# MCORD_Hub.net
KiCad netlist of a schematic drawn in Altium Designer
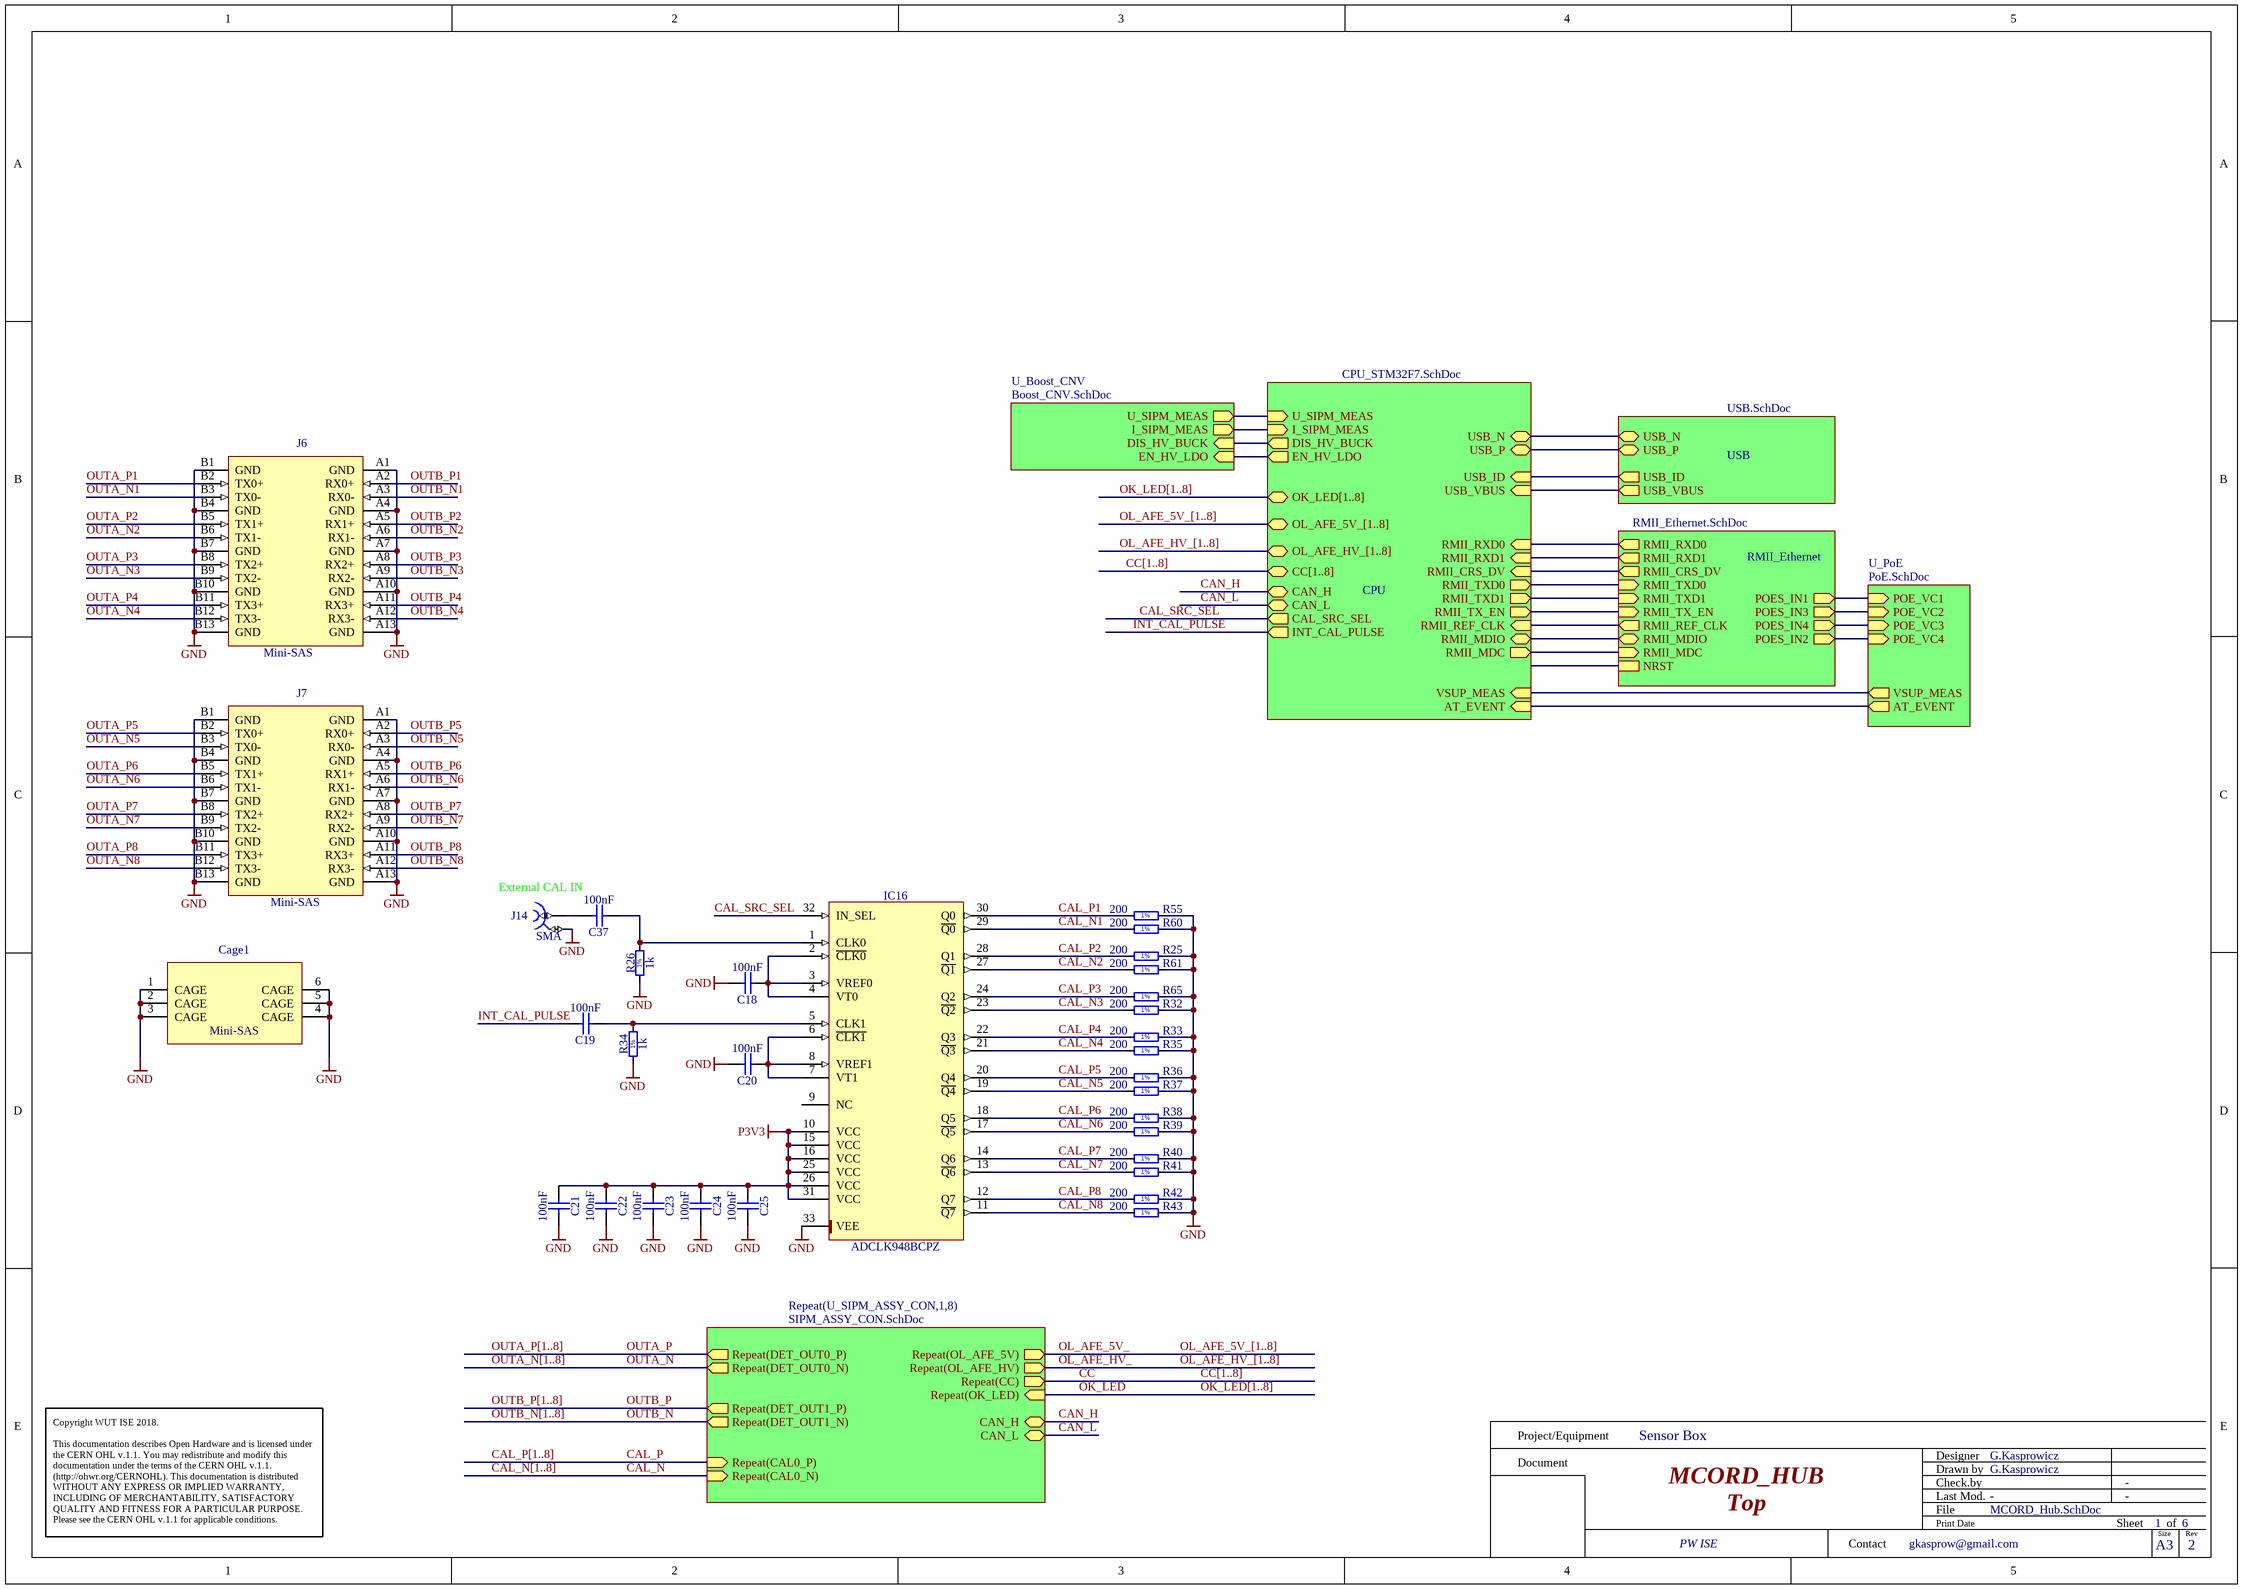
[diagram p0: MCORD_Hub.SchDoc]

(export (version "E")
  (design (tool "Eeschema 10.0.6"))
  (components
    (comp (ref "C18")
      (value "100nF")
      (footprint "CAPC1005X55N")
      (description "Non-polarised capacitor")
      (fields
        (field (name "PART NUMBER") "CC0402_100NF_16V_10%_X7R")
        (field (name "VOLTAGE") "16V")
        (field (name "AUTHOR") "CERN DEM JLC")
      )
      (libsource (lib "Capacitors") (part "Capacitor - non polarized"))
    )
    (comp (ref "C19")
      (value "100nF")
      (footprint "CAPC1005X55N")
      (description "Non-polarised capacitor")
      (fields
        (field (name "PART NUMBER") "CC0402_100NF_16V_10%_X7R")
        (field (name "VOLTAGE") "16V")
        (field (name "AUTHOR") "CERN DEM JLC")
      )
      (libsource (lib "Capacitors") (part "Capacitor - non polarized"))
    )
    (comp (ref "C20")
      (value "100nF")
      (footprint "CAPC1005X55N")
      (description "Non-polarised capacitor")
      (fields
        (field (name "PART NUMBER") "CC0402_100NF_16V_10%_X7R")
        (field (name "VOLTAGE") "16V")
        (field (name "AUTHOR") "CERN DEM JLC")
      )
      (libsource (lib "Capacitors") (part "Capacitor - non polarized"))
    )
    (comp (ref "C21")
      (value "100nF")
      (footprint "CAPC1005X55N")
      (description "Non-polarised capacitor")
      (fields
        (field (name "PART NUMBER") "CC0402_100NF_16V_10%_X7R")
        (field (name "VOLTAGE") "16V")
        (field (name "AUTHOR") "CERN DEM JLC")
      )
      (libsource (lib "Capacitors") (part "Capacitor - non polarized"))
    )
    (comp (ref "C22")
      (value "100nF")
      (footprint "CAPC1005X55N")
      (description "Non-polarised capacitor")
      (fields
        (field (name "PART NUMBER") "CC0402_100NF_16V_10%_X7R")
        (field (name "VOLTAGE") "16V")
        (field (name "AUTHOR") "CERN DEM JLC")
      )
      (libsource (lib "Capacitors") (part "Capacitor - non polarized"))
    )
    (comp (ref "C23")
      (value "100nF")
      (footprint "CAPC1005X55N")
      (description "Non-polarised capacitor")
      (fields
        (field (name "PART NUMBER") "CC0402_100NF_16V_10%_X7R")
        (field (name "VOLTAGE") "16V")
        (field (name "AUTHOR") "CERN DEM JLC")
      )
      (libsource (lib "Capacitors") (part "Capacitor - non polarized"))
    )
    (comp (ref "C24")
      (value "100nF")
      (footprint "CAPC1005X55N")
      (description "Non-polarised capacitor")
      (fields
        (field (name "PART NUMBER") "CC0402_100NF_16V_10%_X7R")
        (field (name "VOLTAGE") "16V")
        (field (name "AUTHOR") "CERN DEM JLC")
      )
      (libsource (lib "Capacitors") (part "Capacitor - non polarized"))
    )
    (comp (ref "C25")
      (value "100nF")
      (footprint "CAPC1005X55N")
      (description "Non-polarised capacitor")
      (fields
        (field (name "PART NUMBER") "CC0402_100NF_16V_10%_X7R")
        (field (name "VOLTAGE") "16V")
        (field (name "AUTHOR") "CERN DEM JLC")
      )
      (libsource (lib "Capacitors") (part "Capacitor - non polarized"))
    )
    (comp (ref "C37")
      (value "100nF")
      (footprint "CAPC1005X55N")
      (description "Non-polarised capacitor")
      (fields
        (field (name "PART NUMBER") "CC0402_100NF_16V_10%_X7R")
        (field (name "VOLTAGE") "16V")
        (field (name "AUTHOR") "CERN DEM JLC")
      )
      (libsource (lib "Capacitors") (part "Capacitor - non polarized"))
    )
    (comp (ref "Cage1")
      (value "Mini-SAS")
      (footprint "TYCO_1888321-2")
      (description "Mini-SAS Cage (6Pins)")
      (fields
        (field (name "PART NUMBER") "TYCO_1888321-2")
        (field (name "MANUFACTURER") "TYCO ELECTRONICS")
        (field (name "AUTHOR") "CERN DEM BC")
      )
      (libsource (lib "Connectors") (part "Mini-SAS Cage (6Pins)"))
    )
    (comp (ref "IC16")
      (value "ADCLK948BCPZ")
      (footprint "QFN50P500X500X80-33N-S285")
      (description "Two Selectable Inputs, 8 LVPECL Outputs, SiGe Clock Fanout Buffer")
      (fields (field (name "MANUFACTURER") "ANALOG DEVICES") (field (name "AUTHOR") "CERN DEM MR"))
      (libsource (lib "ICs And Semiconductors") (part "ADCLK948"))
    )
    (comp (ref "J6")
      (value "Mini-SAS")
      (footprint "TYCO_1761987-7")
      (description "26 Position Mini-Sas Connector (Quad Small Form-Factor SFF-8088)")
      (fields
        (field (name "PART NUMBER") "TYCO_1761987-7")
        (field (name "MANUFACTURER") "TYCO ELECTRONICS")
        (field (name "AUTHOR") "CERN DEM MR")
      )
      (libsource (lib "Connectors") (part "Mini-SAS"))
    )
    (comp (ref "J7")
      (value "Mini-SAS")
      (footprint "TYCO_1761987-7")
      (description "26 Position Mini-Sas Connector (Quad Small Form-Factor SFF-8088)")
      (fields
        (field (name "PART NUMBER") "TYCO_1761987-7")
        (field (name "MANUFACTURER") "TYCO ELECTRONICS")
        (field (name "AUTHOR") "CERN DEM MR")
      )
      (libsource (lib "Connectors") (part "Mini-SAS"))
    )
    (comp (ref "J14")
      (value "SMA")
      (footprint "RF249BT0050GHDW")
      (description "50 Ohm Through Hole SMA Right Angle PCB Jack")
      (fields
        (field (name "PART NUMBER") "AdamTech_RF249BT0050GHDW")
        (field (name "MANUFACTURER") "AdamTech / Molex")
        (field (name "AUTHOR") "GK")
      )
      (libsource (lib "LIBRARY_SCH") (part "CON_SMA_RF249BT0050GHDW"))
    )
    (comp (ref "R25")
      (value "200")
      (footprint "RESC1005X40N")
      (description "Resistor - 1%")
      (fields
        (field (name "PART NUMBER") "R0402_200R_1%_0.0625W_100PPM")
        (field (name "POWER") "0.0625W")
        (field (name "AUTHOR") "CERN DEM JLC")
      )
      (libsource (lib "Resistors") (part "Resistor - 1%"))
    )
    (comp (ref "R26")
      (value "1k")
      (footprint "RESC1005X40N")
      (description "Resistor - 1%")
      (fields
        (field (name "PART NUMBER") "R0402_1K_1%_0.0625W_100PPM")
        (field (name "POWER") "0.0625W")
        (field (name "AUTHOR") "CERN DEM JLC")
      )
      (libsource (lib "Resistors") (part "Resistor - 1%"))
    )
    (comp (ref "R32")
      (value "200")
      (footprint "RESC1005X40N")
      (description "Resistor - 1%")
      (fields
        (field (name "PART NUMBER") "R0402_200R_1%_0.0625W_100PPM")
        (field (name "POWER") "0.0625W")
        (field (name "AUTHOR") "CERN DEM JLC")
      )
      (libsource (lib "Resistors") (part "Resistor - 1%"))
    )
    (comp (ref "R33")
      (value "200")
      (footprint "RESC1005X40N")
      (description "Resistor - 1%")
      (fields
        (field (name "PART NUMBER") "R0402_200R_1%_0.0625W_100PPM")
        (field (name "POWER") "0.0625W")
        (field (name "AUTHOR") "CERN DEM JLC")
      )
      (libsource (lib "Resistors") (part "Resistor - 1%"))
    )
    (comp (ref "R34")
      (value "1k")
      (footprint "RESC1005X40N")
      (description "Resistor - 1%")
      (fields
        (field (name "PART NUMBER") "R0402_1K_1%_0.0625W_100PPM")
        (field (name "POWER") "0.0625W")
        (field (name "AUTHOR") "CERN DEM JLC")
      )
      (libsource (lib "Resistors") (part "Resistor - 1%"))
    )
    (comp (ref "R35")
      (value "200")
      (footprint "RESC1005X40N")
      (description "Resistor - 1%")
      (fields
        (field (name "PART NUMBER") "R0402_200R_1%_0.0625W_100PPM")
        (field (name "POWER") "0.0625W")
        (field (name "AUTHOR") "CERN DEM JLC")
      )
      (libsource (lib "Resistors") (part "Resistor - 1%"))
    )
    (comp (ref "R36")
      (value "200")
      (footprint "RESC1005X40N")
      (description "Resistor - 1%")
      (fields
        (field (name "PART NUMBER") "R0402_200R_1%_0.0625W_100PPM")
        (field (name "POWER") "0.0625W")
        (field (name "AUTHOR") "CERN DEM JLC")
      )
      (libsource (lib "Resistors") (part "Resistor - 1%"))
    )
    (comp (ref "R37")
      (value "200")
      (footprint "RESC1005X40N")
      (description "Resistor - 1%")
      (fields
        (field (name "PART NUMBER") "R0402_200R_1%_0.0625W_100PPM")
        (field (name "POWER") "0.0625W")
        (field (name "AUTHOR") "CERN DEM JLC")
      )
      (libsource (lib "Resistors") (part "Resistor - 1%"))
    )
    (comp (ref "R38")
      (value "200")
      (footprint "RESC1005X40N")
      (description "Resistor - 1%")
      (fields
        (field (name "PART NUMBER") "R0402_200R_1%_0.0625W_100PPM")
        (field (name "POWER") "0.0625W")
        (field (name "AUTHOR") "CERN DEM JLC")
      )
      (libsource (lib "Resistors") (part "Resistor - 1%"))
    )
    (comp (ref "R39")
      (value "200")
      (footprint "RESC1005X40N")
      (description "Resistor - 1%")
      (fields
        (field (name "PART NUMBER") "R0402_200R_1%_0.0625W_100PPM")
        (field (name "POWER") "0.0625W")
        (field (name "AUTHOR") "CERN DEM JLC")
      )
      (libsource (lib "Resistors") (part "Resistor - 1%"))
    )
    (comp (ref "R40")
      (value "200")
      (footprint "RESC1005X40N")
      (description "Resistor - 1%")
      (fields
        (field (name "PART NUMBER") "R0402_200R_1%_0.0625W_100PPM")
        (field (name "POWER") "0.0625W")
        (field (name "AUTHOR") "CERN DEM JLC")
      )
      (libsource (lib "Resistors") (part "Resistor - 1%"))
    )
    (comp (ref "R41")
      (value "200")
      (footprint "RESC1005X40N")
      (description "Resistor - 1%")
      (fields
        (field (name "PART NUMBER") "R0402_200R_1%_0.0625W_100PPM")
        (field (name "POWER") "0.0625W")
        (field (name "AUTHOR") "CERN DEM JLC")
      )
      (libsource (lib "Resistors") (part "Resistor - 1%"))
    )
    (comp (ref "R42")
      (value "200")
      (footprint "RESC1005X40N")
      (description "Resistor - 1%")
      (fields
        (field (name "PART NUMBER") "R0402_200R_1%_0.0625W_100PPM")
        (field (name "POWER") "0.0625W")
        (field (name "AUTHOR") "CERN DEM JLC")
      )
      (libsource (lib "Resistors") (part "Resistor - 1%"))
    )
    (comp (ref "R43")
      (value "200")
      (footprint "RESC1005X40N")
      (description "Resistor - 1%")
      (fields
        (field (name "PART NUMBER") "R0402_200R_1%_0.0625W_100PPM")
        (field (name "POWER") "0.0625W")
        (field (name "AUTHOR") "CERN DEM JLC")
      )
      (libsource (lib "Resistors") (part "Resistor - 1%"))
    )
    (comp (ref "R55")
      (value "200")
      (footprint "RESC1005X40N")
      (description "Resistor - 1%")
      (fields
        (field (name "PART NUMBER") "R0402_200R_1%_0.0625W_100PPM")
        (field (name "POWER") "0.0625W")
        (field (name "AUTHOR") "CERN DEM JLC")
      )
      (libsource (lib "Resistors") (part "Resistor - 1%"))
    )
    (comp (ref "R60")
      (value "200")
      (footprint "RESC1005X40N")
      (description "Resistor - 1%")
      (fields
        (field (name "PART NUMBER") "R0402_200R_1%_0.0625W_100PPM")
        (field (name "POWER") "0.0625W")
        (field (name "AUTHOR") "CERN DEM JLC")
      )
      (libsource (lib "Resistors") (part "Resistor - 1%"))
    )
    (comp (ref "R61")
      (value "200")
      (footprint "RESC1005X40N")
      (description "Resistor - 1%")
      (fields
        (field (name "PART NUMBER") "R0402_200R_1%_0.0625W_100PPM")
        (field (name "POWER") "0.0625W")
        (field (name "AUTHOR") "CERN DEM JLC")
      )
      (libsource (lib "Resistors") (part "Resistor - 1%"))
    )
    (comp (ref "R65")
      (value "200")
      (footprint "RESC1005X40N")
      (description "Resistor - 1%")
      (fields
        (field (name "PART NUMBER") "R0402_200R_1%_0.0625W_100PPM")
        (field (name "POWER") "0.0625W")
        (field (name "AUTHOR") "CERN DEM JLC")
      )
      (libsource (lib "Resistors") (part "Resistor - 1%"))
    )
  )
  (nets
    (net (code "35") (name "/CAL_N1") (class "Default")
      (node (ref "IC16") (pin "29") (pinfunction "~{Q0}_29") (pintype "output"))
      (node (ref "R60") (pin "1") (pinfunction "1_1") (pintype "passive"))
    )
    (net (code "36") (name "/CAL_N2") (class "Default")
      (node (ref "IC16") (pin "27") (pinfunction "~{Q1}_27") (pintype "output"))
      (node (ref "R61") (pin "1") (pinfunction "1_1") (pintype "passive"))
    )
    (net (code "37") (name "/CAL_N3") (class "Default")
      (node (ref "IC16") (pin "23") (pinfunction "~{Q2}_23") (pintype "output"))
      (node (ref "R32") (pin "1") (pinfunction "1_1") (pintype "passive"))
    )
    (net (code "38") (name "/CAL_N4") (class "Default")
      (node (ref "IC16") (pin "21") (pinfunction "~{Q3}_21") (pintype "output"))
      (node (ref "R35") (pin "1") (pinfunction "1_1") (pintype "passive"))
    )
    (net (code "39") (name "/CAL_N5") (class "Default")
      (node (ref "IC16") (pin "19") (pinfunction "~{Q4}_19") (pintype "output"))
      (node (ref "R37") (pin "1") (pinfunction "1_1") (pintype "passive"))
    )
    (net (code "40") (name "/CAL_N6") (class "Default")
      (node (ref "IC16") (pin "17") (pinfunction "~{Q5}_17") (pintype "output"))
      (node (ref "R39") (pin "1") (pinfunction "1_1") (pintype "passive"))
    )
    (net (code "41") (name "/CAL_N7") (class "Default")
      (node (ref "IC16") (pin "13") (pinfunction "~{Q6}_13") (pintype "output"))
      (node (ref "R41") (pin "1") (pinfunction "1_1") (pintype "passive"))
    )
    (net (code "42") (name "/CAL_N8") (class "Default")
      (node (ref "IC16") (pin "11") (pinfunction "~{Q7}_11") (pintype "output"))
      (node (ref "R43") (pin "1") (pinfunction "1_1") (pintype "passive"))
    )
    (net (code "45") (name "/CAL_P1") (class "Default")
      (node (ref "IC16") (pin "30") (pinfunction "Q0_30") (pintype "output"))
      (node (ref "R55") (pin "1") (pinfunction "1_1") (pintype "passive"))
    )
    (net (code "46") (name "/CAL_P2") (class "Default")
      (node (ref "IC16") (pin "28") (pinfunction "Q1_28") (pintype "output"))
      (node (ref "R25") (pin "1") (pinfunction "1_1") (pintype "passive"))
    )
    (net (code "47") (name "/CAL_P3") (class "Default")
      (node (ref "IC16") (pin "24") (pinfunction "Q2_24") (pintype "output"))
      (node (ref "R65") (pin "1") (pinfunction "1_1") (pintype "passive"))
    )
    (net (code "48") (name "/CAL_P4") (class "Default")
      (node (ref "IC16") (pin "22") (pinfunction "Q3_22") (pintype "output"))
      (node (ref "R33") (pin "1") (pinfunction "1_1") (pintype "passive"))
    )
    (net (code "49") (name "/CAL_P5") (class "Default")
      (node (ref "IC16") (pin "20") (pinfunction "Q4_20") (pintype "output"))
      (node (ref "R36") (pin "1") (pinfunction "1_1") (pintype "passive"))
    )
    (net (code "50") (name "/CAL_P6") (class "Default")
      (node (ref "IC16") (pin "18") (pinfunction "Q5_18") (pintype "output"))
      (node (ref "R38") (pin "1") (pinfunction "1_1") (pintype "passive"))
    )
    (net (code "51") (name "/CAL_P7") (class "Default")
      (node (ref "IC16") (pin "14") (pinfunction "Q6_14") (pintype "output"))
      (node (ref "R40") (pin "1") (pinfunction "1_1") (pintype "passive"))
    )
    (net (code "52") (name "/CAL_P8") (class "Default")
      (node (ref "IC16") (pin "12") (pinfunction "Q7_12") (pintype "output"))
      (node (ref "R42") (pin "1") (pinfunction "1_1") (pintype "passive"))
    )
    (net (code "54") (name "/CAL_SRC_SEL") (class "Default")
      (node (ref "IC16") (pin "32") (pinfunction "IN_SEL_32") (pintype "input"))
    )
    (net (code "61") (name "/INT_CAL_PULSE") (class "Default")
      (node (ref "C19") (pin "2") (pinfunction "2_2") (pintype "passive"))
    )
    (net (code "71") (name "/OUTA_N1") (class "Default")
      (node (ref "J6") (pin "B3") (pinfunction "TX0-_B3") (pintype "input"))
    )
    (net (code "72") (name "/OUTA_N2") (class "Default")
      (node (ref "J6") (pin "B6") (pinfunction "TX1-_B6") (pintype "input"))
    )
    (net (code "73") (name "/OUTA_N3") (class "Default")
      (node (ref "J6") (pin "B9") (pinfunction "TX2-_B9") (pintype "input"))
    )
    (net (code "74") (name "/OUTA_N4") (class "Default")
      (node (ref "J6") (pin "B12") (pinfunction "TX3-_B12") (pintype "input"))
    )
    (net (code "75") (name "/OUTA_N5") (class "Default")
      (node (ref "J7") (pin "B3") (pinfunction "TX0-_B3") (pintype "input"))
    )
    (net (code "76") (name "/OUTA_N6") (class "Default")
      (node (ref "J7") (pin "B6") (pinfunction "TX1-_B6") (pintype "input"))
    )
    (net (code "77") (name "/OUTA_N7") (class "Default")
      (node (ref "J7") (pin "B9") (pinfunction "TX2-_B9") (pintype "input"))
    )
    (net (code "78") (name "/OUTA_N8") (class "Default")
      (node (ref "J7") (pin "B12") (pinfunction "TX3-_B12") (pintype "input"))
    )
    (net (code "81") (name "/OUTA_P1") (class "Default")
      (node (ref "J6") (pin "B2") (pinfunction "TX0+_B2") (pintype "input"))
    )
    (net (code "82") (name "/OUTA_P2") (class "Default")
      (node (ref "J6") (pin "B5") (pinfunction "TX1+_B5") (pintype "input"))
    )
    (net (code "83") (name "/OUTA_P3") (class "Default")
      (node (ref "J6") (pin "B8") (pinfunction "TX2+_B8") (pintype "input"))
    )
    (net (code "84") (name "/OUTA_P4") (class "Default")
      (node (ref "J6") (pin "B11") (pinfunction "TX3+_B11") (pintype "input"))
    )
    (net (code "85") (name "/OUTA_P5") (class "Default")
      (node (ref "J7") (pin "B2") (pinfunction "TX0+_B2") (pintype "input"))
    )
    (net (code "86") (name "/OUTA_P6") (class "Default")
      (node (ref "J7") (pin "B5") (pinfunction "TX1+_B5") (pintype "input"))
    )
    (net (code "87") (name "/OUTA_P7") (class "Default")
      (node (ref "J7") (pin "B8") (pinfunction "TX2+_B8") (pintype "input"))
    )
    (net (code "88") (name "/OUTA_P8") (class "Default")
      (node (ref "J7") (pin "B11") (pinfunction "TX3+_B11") (pintype "input"))
    )
    (net (code "91") (name "/OUTB_N1") (class "Default")
      (node (ref "J6") (pin "A3") (pinfunction "RX0-_A3") (pintype "input"))
    )
    (net (code "92") (name "/OUTB_N2") (class "Default")
      (node (ref "J6") (pin "A6") (pinfunction "RX1-_A6") (pintype "input"))
    )
    (net (code "93") (name "/OUTB_N3") (class "Default")
      (node (ref "J6") (pin "A9") (pinfunction "RX2-_A9") (pintype "input"))
    )
    (net (code "94") (name "/OUTB_N4") (class "Default")
      (node (ref "J6") (pin "A12") (pinfunction "RX3-_A12") (pintype "input"))
    )
    (net (code "95") (name "/OUTB_N5") (class "Default")
      (node (ref "J7") (pin "A3") (pinfunction "RX0-_A3") (pintype "input"))
    )
    (net (code "96") (name "/OUTB_N6") (class "Default")
      (node (ref "J7") (pin "A6") (pinfunction "RX1-_A6") (pintype "input"))
    )
    (net (code "97") (name "/OUTB_N7") (class "Default")
      (node (ref "J7") (pin "A9") (pinfunction "RX2-_A9") (pintype "input"))
    )
    (net (code "98") (name "/OUTB_N8") (class "Default")
      (node (ref "J7") (pin "A12") (pinfunction "RX3-_A12") (pintype "input"))
    )
    (net (code "101") (name "/OUTB_P1") (class "Default")
      (node (ref "J6") (pin "A2") (pinfunction "RX0+_A2") (pintype "input"))
    )
    (net (code "102") (name "/OUTB_P2") (class "Default")
      (node (ref "J6") (pin "A5") (pinfunction "RX1+_A5") (pintype "input"))
    )
    (net (code "103") (name "/OUTB_P3") (class "Default")
      (node (ref "J6") (pin "A8") (pinfunction "RX2+_A8") (pintype "input"))
    )
    (net (code "104") (name "/OUTB_P4") (class "Default")
      (node (ref "J6") (pin "A11") (pinfunction "RX3+_A11") (pintype "input"))
    )
    (net (code "105") (name "/OUTB_P5") (class "Default")
      (node (ref "J7") (pin "A2") (pinfunction "RX0+_A2") (pintype "input"))
    )
    (net (code "106") (name "/OUTB_P6") (class "Default")
      (node (ref "J7") (pin "A5") (pinfunction "RX1+_A5") (pintype "input"))
    )
    (net (code "107") (name "/OUTB_P7") (class "Default")
      (node (ref "J7") (pin "A8") (pinfunction "RX2+_A8") (pintype "input"))
    )
    (net (code "108") (name "/OUTB_P8") (class "Default")
      (node (ref "J7") (pin "A11") (pinfunction "RX3+_A11") (pintype "input"))
    )
    (net (code "129") (name "GND") (class "Default")
      (node (ref "C18") (pin "2") (pinfunction "2_2") (pintype "passive"))
      (node (ref "C20") (pin "2") (pinfunction "2_2") (pintype "passive"))
      (node (ref "C21") (pin "2") (pinfunction "2_2") (pintype "passive"))
      (node (ref "C22") (pin "2") (pinfunction "2_2") (pintype "passive"))
      (node (ref "C23") (pin "2") (pinfunction "2_2") (pintype "passive"))
      (node (ref "C24") (pin "2") (pinfunction "2_2") (pintype "passive"))
      (node (ref "C25") (pin "2") (pinfunction "2_2") (pintype "passive"))
      (node (ref "Cage1") (pin "1") (pinfunction "CAGE_1") (pintype "power_in"))
      (node (ref "Cage1") (pin "2") (pinfunction "CAGE_2") (pintype "power_in"))
      (node (ref "Cage1") (pin "3") (pinfunction "CAGE_3") (pintype "power_in"))
      (node (ref "Cage1") (pin "4") (pinfunction "CAGE_4") (pintype "power_in"))
      (node (ref "Cage1") (pin "5") (pinfunction "CAGE_5") (pintype "power_in"))
      (node (ref "Cage1") (pin "6") (pinfunction "CAGE_6") (pintype "power_in"))
      (node (ref "IC16") (pin "33") (pinfunction "VEE_33") (pintype "power_in"))
      (node (ref "J14") (pin "2") (pinfunction "2_2") (pintype "bidirectional"))
      (node (ref "J6") (pin "A1") (pinfunction "GND_A1") (pintype "power_in"))
      (node (ref "J6") (pin "A10") (pinfunction "GND_A10") (pintype "power_in"))
      (node (ref "J6") (pin "A13") (pinfunction "GND_A13") (pintype "power_in"))
      (node (ref "J6") (pin "A4") (pinfunction "GND_A4") (pintype "power_in"))
      (node (ref "J6") (pin "A7") (pinfunction "GND_A7") (pintype "power_in"))
      (node (ref "J6") (pin "B1") (pinfunction "GND_B1") (pintype "power_in"))
      (node (ref "J6") (pin "B10") (pinfunction "GND_B10") (pintype "power_in"))
      (node (ref "J6") (pin "B13") (pinfunction "GND_B13") (pintype "power_in"))
      (node (ref "J6") (pin "B4") (pinfunction "GND_B4") (pintype "power_in"))
      (node (ref "J6") (pin "B7") (pinfunction "GND_B7") (pintype "power_in"))
      (node (ref "J7") (pin "A1") (pinfunction "GND_A1") (pintype "power_in"))
      (node (ref "J7") (pin "A10") (pinfunction "GND_A10") (pintype "power_in"))
      (node (ref "J7") (pin "A13") (pinfunction "GND_A13") (pintype "power_in"))
      (node (ref "J7") (pin "A4") (pinfunction "GND_A4") (pintype "power_in"))
      (node (ref "J7") (pin "A7") (pinfunction "GND_A7") (pintype "power_in"))
      (node (ref "J7") (pin "B1") (pinfunction "GND_B1") (pintype "power_in"))
      (node (ref "J7") (pin "B10") (pinfunction "GND_B10") (pintype "power_in"))
      (node (ref "J7") (pin "B13") (pinfunction "GND_B13") (pintype "power_in"))
      (node (ref "J7") (pin "B4") (pinfunction "GND_B4") (pintype "power_in"))
      (node (ref "J7") (pin "B7") (pinfunction "GND_B7") (pintype "power_in"))
      (node (ref "R25") (pin "2") (pinfunction "2_2") (pintype "passive"))
      (node (ref "R26") (pin "1") (pinfunction "1_1") (pintype "passive"))
      (node (ref "R32") (pin "2") (pinfunction "2_2") (pintype "passive"))
      (node (ref "R33") (pin "2") (pinfunction "2_2") (pintype "passive"))
      (node (ref "R34") (pin "1") (pinfunction "1_1") (pintype "passive"))
      (node (ref "R35") (pin "2") (pinfunction "2_2") (pintype "passive"))
      (node (ref "R36") (pin "2") (pinfunction "2_2") (pintype "passive"))
      (node (ref "R37") (pin "2") (pinfunction "2_2") (pintype "passive"))
      (node (ref "R38") (pin "2") (pinfunction "2_2") (pintype "passive"))
      (node (ref "R39") (pin "2") (pinfunction "2_2") (pintype "passive"))
      (node (ref "R40") (pin "2") (pinfunction "2_2") (pintype "passive"))
      (node (ref "R41") (pin "2") (pinfunction "2_2") (pintype "passive"))
      (node (ref "R42") (pin "2") (pinfunction "2_2") (pintype "passive"))
      (node (ref "R43") (pin "2") (pinfunction "2_2") (pintype "passive"))
      (node (ref "R55") (pin "2") (pinfunction "2_2") (pintype "passive"))
      (node (ref "R60") (pin "2") (pinfunction "2_2") (pintype "passive"))
      (node (ref "R61") (pin "2") (pinfunction "2_2") (pintype "passive"))
      (node (ref "R65") (pin "2") (pinfunction "2_2") (pintype "passive"))
    )
    (net (code "130") (name "Net-(C37-Pad2)") (class "Default")
      (node (ref "C37") (pin "2") (pinfunction "2_2") (pintype "passive"))
      (node (ref "J14") (pin "1") (pinfunction "1_1") (pintype "bidirectional"))
    )
    (net (code "131") (name "Net-(IC16-CLK0)") (class "Default")
      (node (ref "C37") (pin "1") (pinfunction "1_1") (pintype "passive"))
      (node (ref "IC16") (pin "1") (pinfunction "CLK0_1") (pintype "input"))
      (node (ref "R26") (pin "2") (pinfunction "2_2") (pintype "passive"))
    )
    (net (code "132") (name "Net-(IC16-CLK1)") (class "Default")
      (node (ref "C19") (pin "1") (pinfunction "1_1") (pintype "passive"))
      (node (ref "IC16") (pin "5") (pinfunction "CLK1_5") (pintype "input"))
      (node (ref "R34") (pin "2") (pinfunction "2_2") (pintype "passive"))
    )
    (net (code "133") (name "Net-(IC16-VREF0)") (class "Default")
      (node (ref "C18") (pin "1") (pinfunction "1_1") (pintype "passive"))
      (node (ref "IC16") (pin "2") (pinfunction "~{CLK0}_2") (pintype "input"))
      (node (ref "IC16") (pin "3") (pinfunction "VREF0_3") (pintype "input"))
      (node (ref "IC16") (pin "4") (pinfunction "VT0_4") (pintype "passive"))
    )
    (net (code "134") (name "Net-(IC16-VREF1)") (class "Default")
      (node (ref "C20") (pin "1") (pinfunction "1_1") (pintype "passive"))
      (node (ref "IC16") (pin "6") (pinfunction "~{CLK1}_6") (pintype "input"))
      (node (ref "IC16") (pin "7") (pinfunction "VT1_7") (pintype "passive"))
      (node (ref "IC16") (pin "8") (pinfunction "VREF1_8") (pintype "input"))
    )
    (net (code "135") (name "P3V3") (class "Default")
      (node (ref "C21") (pin "1") (pinfunction "1_1") (pintype "passive"))
      (node (ref "C22") (pin "1") (pinfunction "1_1") (pintype "passive"))
      (node (ref "C23") (pin "1") (pinfunction "1_1") (pintype "passive"))
      (node (ref "C24") (pin "1") (pinfunction "1_1") (pintype "passive"))
      (node (ref "C25") (pin "1") (pinfunction "1_1") (pintype "passive"))
      (node (ref "IC16") (pin "10") (pinfunction "VCC_10") (pintype "power_in"))
      (node (ref "IC16") (pin "15") (pinfunction "VCC_15") (pintype "power_in"))
      (node (ref "IC16") (pin "16") (pinfunction "VCC_16") (pintype "power_in"))
      (node (ref "IC16") (pin "25") (pinfunction "VCC_25") (pintype "power_in"))
      (node (ref "IC16") (pin "26") (pinfunction "VCC_26") (pintype "power_in"))
      (node (ref "IC16") (pin "31") (pinfunction "VCC_31") (pintype "power_in"))
    )
    (net (code "136") (name "unconnected-(IC16-NC-Pad9)") (class "Default")
      (node (ref "IC16") (pin "9") (pinfunction "NC_9") (pintype "passive"))
    )
  )
)
